# Actuator-MKI-Revision-DT.net
KiCad netlist of a schematic drawn in EAGLE
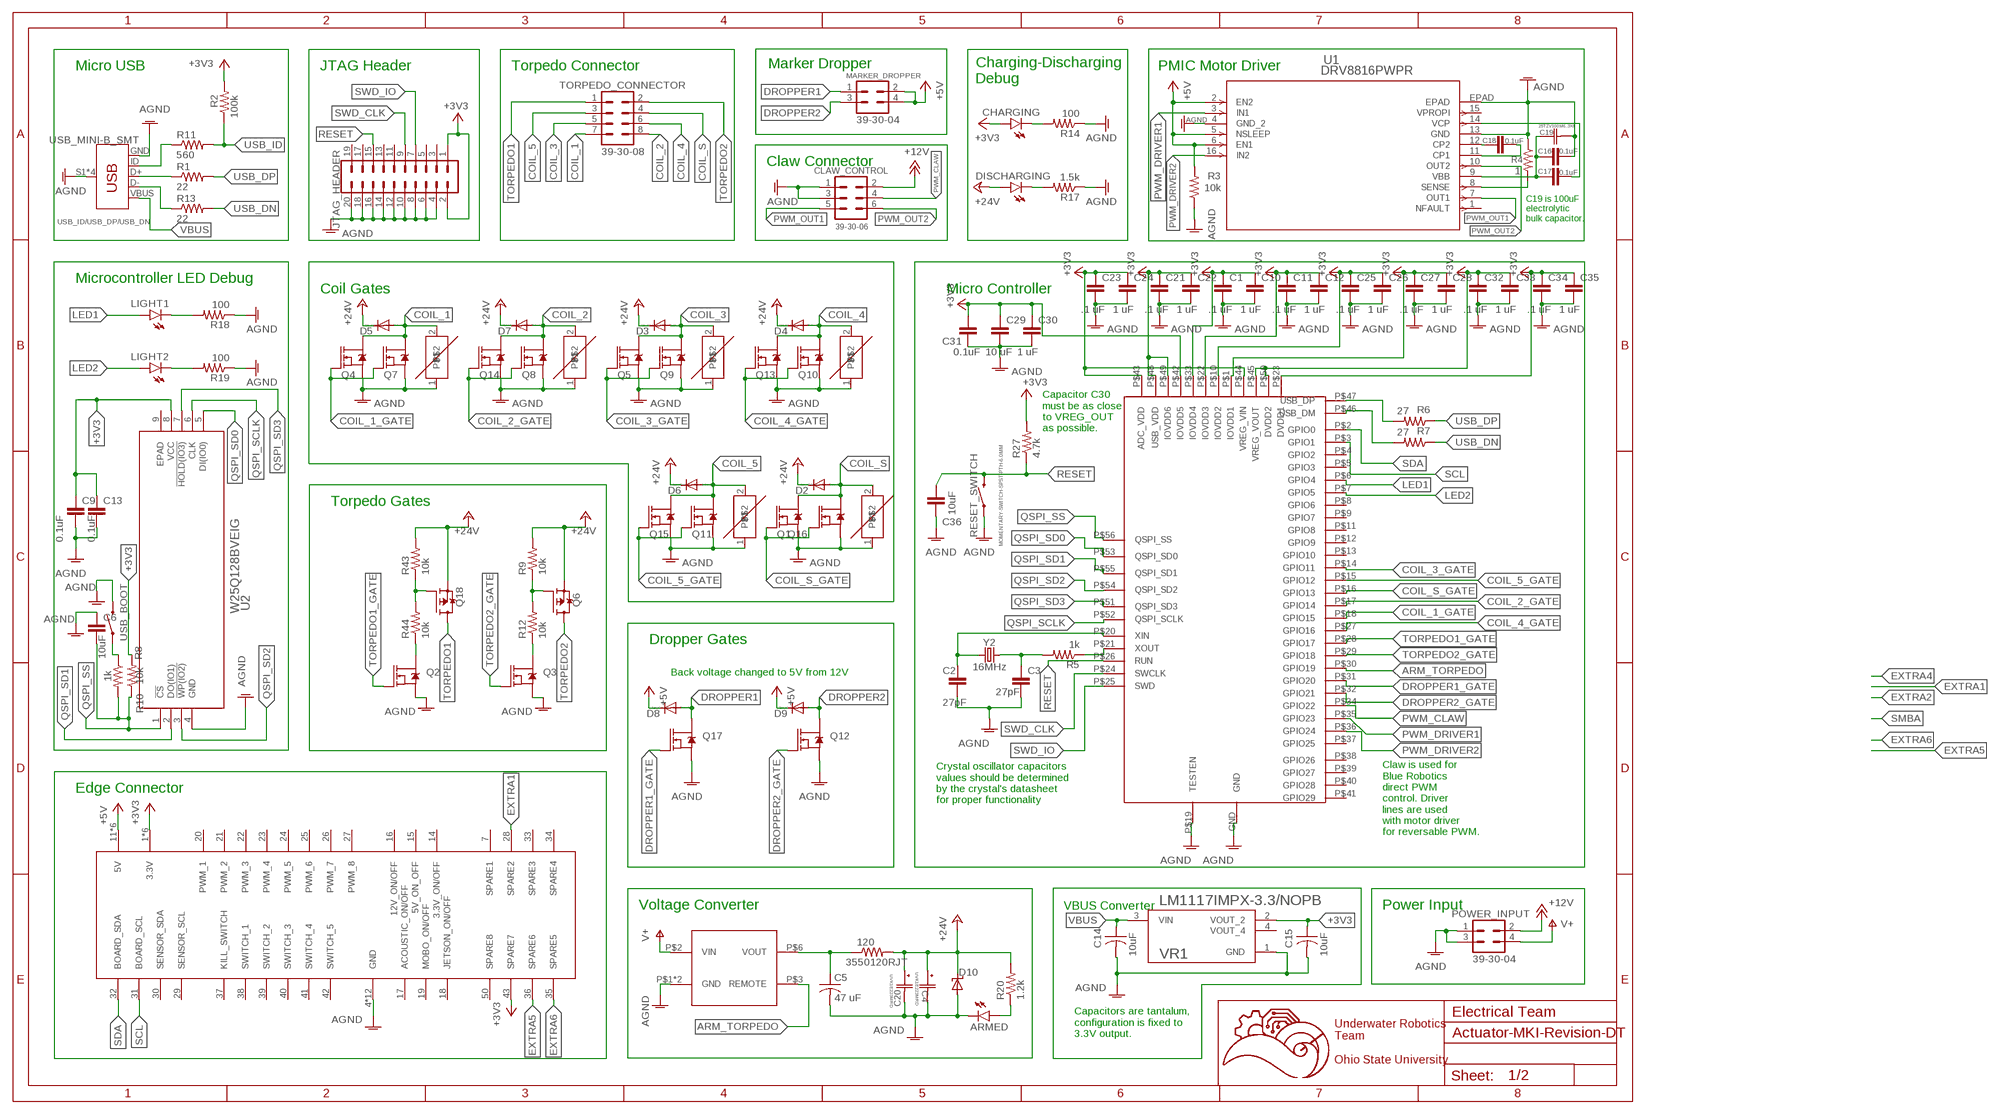
[diagram p0: schematic, sheet 1]
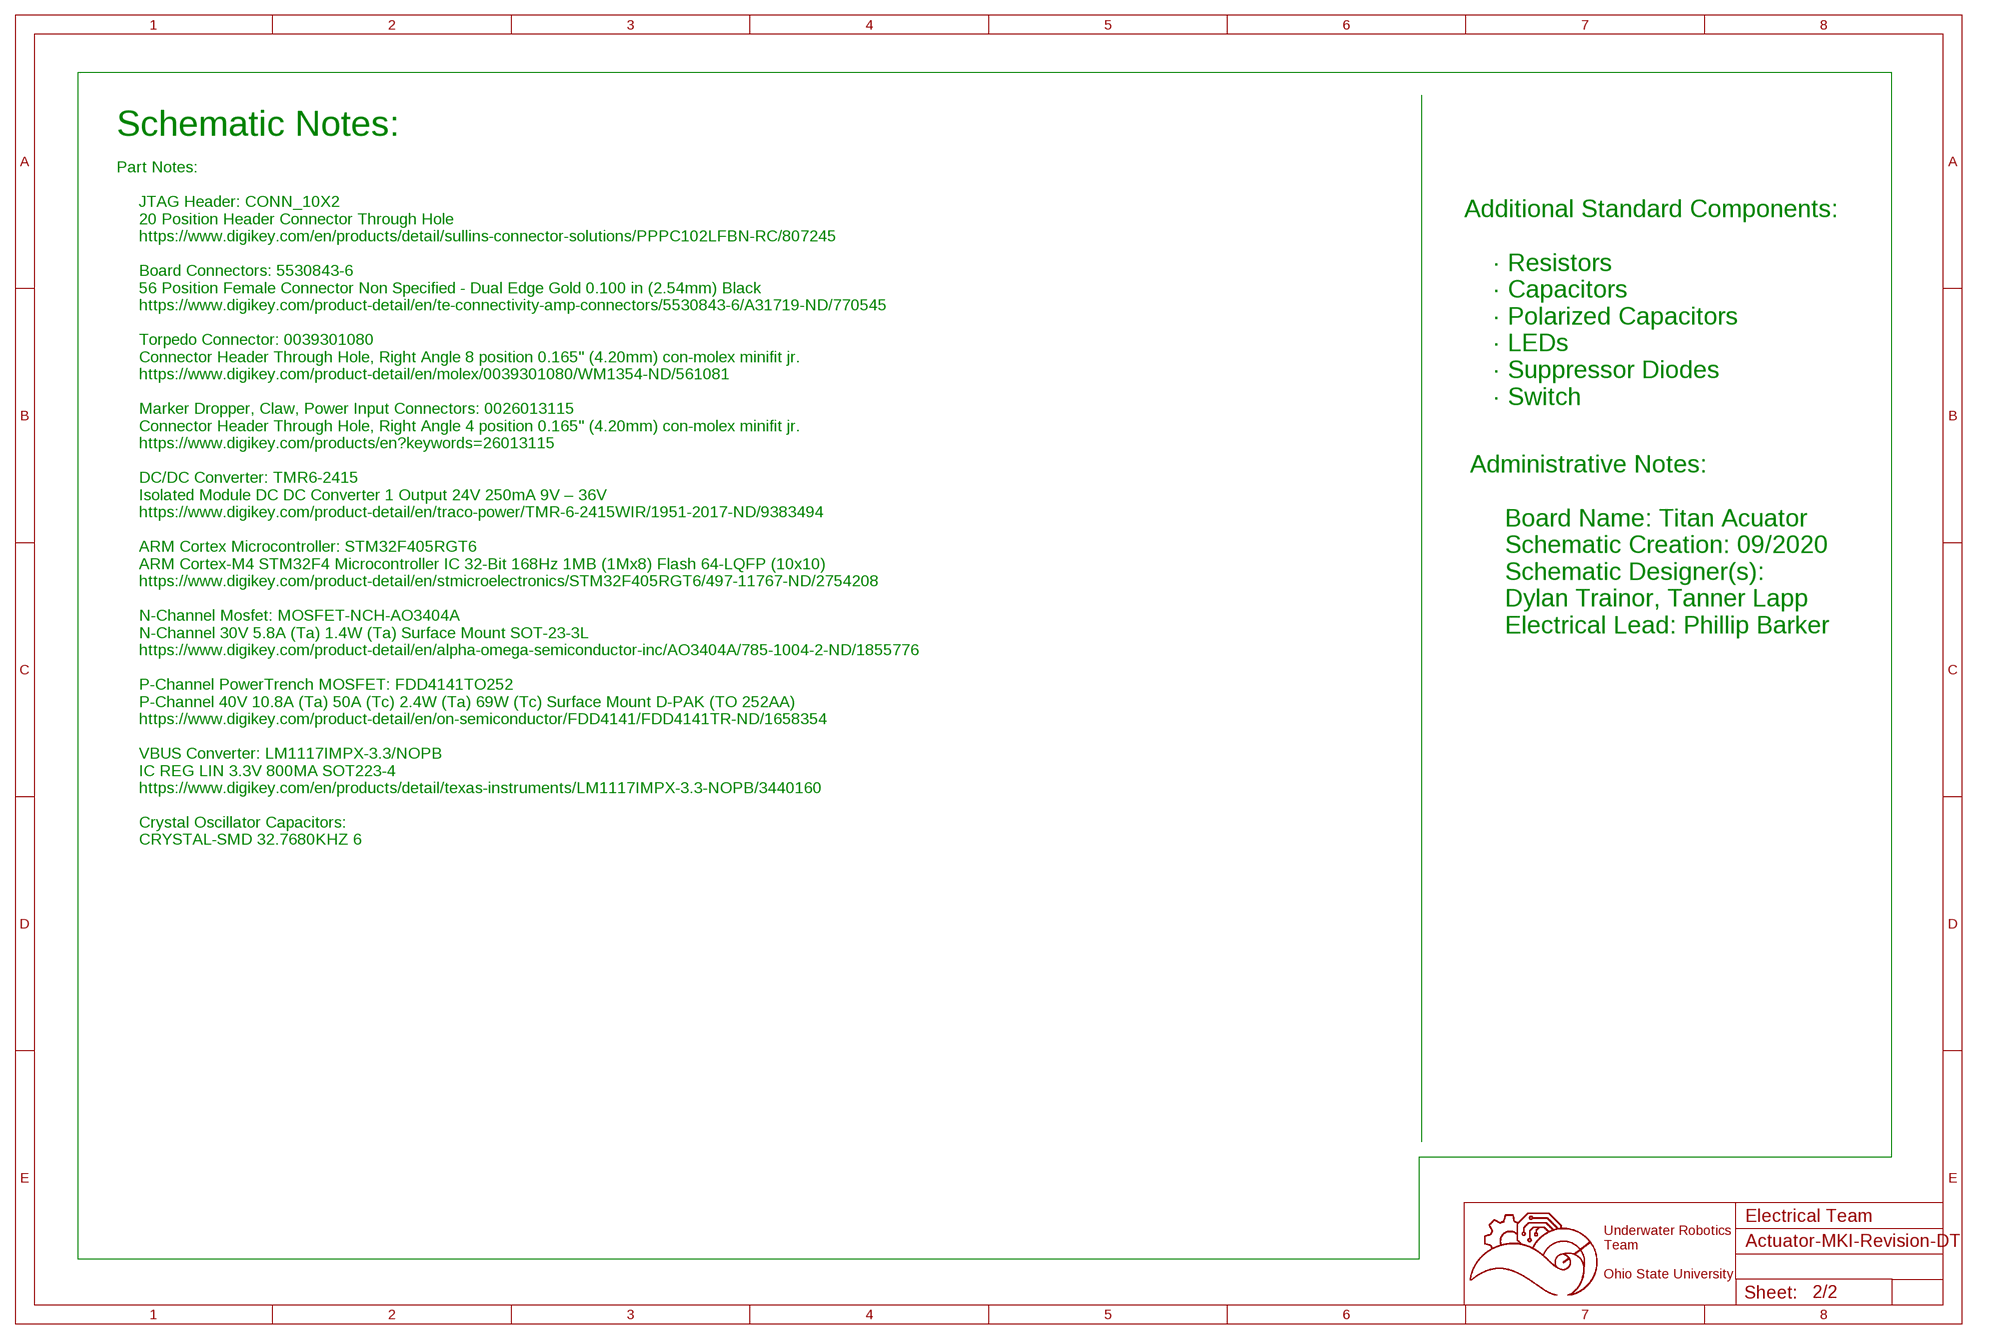
[diagram p1: schematic, sheet 2]

(export (version "E")
  (design (tool "Eeschema 10.0.6"))
  (components
    (comp (ref "120")
      (value "3550120RJT")
      (footprint "eagle-import:3550120RJT")
      (libsource (lib "eagle-import") (part "3550120RJT"))
    )
    (comp (ref "ARMED")
      (value "LEDCHIPLED_0603")
      (footprint "eagle-import:CHIPLED_0603")
      (libsource (lib "eagle-import") (part "LEDCHIPLED_0603"))
    )
    (comp (ref "C1")
      (value ".1 uF")
      (footprint "eagle-import:C0603")
      (libsource (lib "eagle-import") (part "C-EUC0603"))
    )
    (comp (ref "C2")
      (value "27pF")
      (footprint "eagle-import:C0603")
      (libsource (lib "eagle-import") (part "C-EUC0603"))
    )
    (comp (ref "C3")
      (value "27pF")
      (footprint "eagle-import:C0603")
      (libsource (lib "eagle-import") (part "C-EUC0603"))
    )
    (comp (ref "C4")
      (value "UVK1E223MRD")
      (footprint "eagle-import:CAP_UFW_25X50_NCH")
      (fields (field (name "COPYRIGHT") "Copyright (C) 2018 Accelerated Designs. All rights reserved"))
      (libsource (lib "eagle-import") (part "UVK1E223MRD"))
    )
    (comp (ref "C5")
      (value "47 uF")
      (footprint "eagle-import:C1206K")
      (libsource (lib "eagle-import") (part "resistor_348_C-USC1206K"))
    )
    (comp (ref "C6")
      (value "10uF")
      (footprint "eagle-import:C0603")
      (libsource (lib "eagle-import") (part "C-EUC0603"))
    )
    (comp (ref "C9")
      (value "0.1uF")
      (footprint "eagle-import:C0603")
      (libsource (lib "eagle-import") (part "C-EUC0603"))
    )
    (comp (ref "C10")
      (value "1 uF")
      (footprint "eagle-import:C0603")
      (libsource (lib "eagle-import") (part "C-EUC0603"))
    )
    (comp (ref "C11")
      (value ".1 uF")
      (footprint "eagle-import:C0603")
      (libsource (lib "eagle-import") (part "C-EUC0603"))
    )
    (comp (ref "C12")
      (value "1 uF")
      (footprint "eagle-import:C0603")
      (libsource (lib "eagle-import") (part "C-EUC0603"))
    )
    (comp (ref "C13")
      (value "0.1uF")
      (footprint "eagle-import:C0603")
      (libsource (lib "eagle-import") (part "C-EUC0603"))
    )
    (comp (ref "C14")
      (value "10uF")
      (footprint "eagle-import:C0603")
      (libsource (lib "eagle-import") (part "C-USC0603"))
    )
    (comp (ref "C15")
      (value "10uF")
      (footprint "eagle-import:C0603")
      (libsource (lib "eagle-import") (part "C-USC0603"))
    )
    (comp (ref "C16")
      (value "0.1uF")
      (footprint "eagle-import:C0603")
      (libsource (lib "eagle-import") (part "C-EUC0603"))
    )
    (comp (ref "C17")
      (value "0.1uF")
      (footprint "eagle-import:C0603")
      (libsource (lib "eagle-import") (part "C-EUC0603"))
    )
    (comp (ref "C18")
      (value "0.1uF")
      (footprint "eagle-import:C0603")
      (libsource (lib "eagle-import") (part "C-EUC0603"))
    )
    (comp (ref "C19")
      (value "25TZV100M6.3X8")
      (footprint "eagle-import:CAP_J-V_6P3X8_RUB")
      (fields (field (name "COPYRIGHT") "Copyright (C) 2018 Accelerated Designs. All rights reserved"))
      (libsource (lib "eagle-import") (part "25TZV100M6.3X8"))
    )
    (comp (ref "C20")
      (value "UVK1E223MRD")
      (footprint "eagle-import:CAP_UFW_25X50_NCH")
      (fields (field (name "COPYRIGHT") "Copyright (C) 2018 Accelerated Designs. All rights reserved"))
      (libsource (lib "eagle-import") (part "UVK1E223MRD"))
    )
    (comp (ref "C21")
      (value ".1 uF")
      (footprint "eagle-import:C0603")
      (libsource (lib "eagle-import") (part "C-EUC0603"))
    )
    (comp (ref "C22")
      (value "1 uF")
      (footprint "eagle-import:C0603")
      (libsource (lib "eagle-import") (part "C-EUC0603"))
    )
    (comp (ref "C23")
      (value ".1 uF")
      (footprint "eagle-import:C0603")
      (libsource (lib "eagle-import") (part "C-EUC0603"))
    )
    (comp (ref "C24")
      (value "1 uF")
      (footprint "eagle-import:C0603")
      (libsource (lib "eagle-import") (part "C-EUC0603"))
    )
    (comp (ref "C25")
      (value ".1 uF")
      (footprint "eagle-import:C0603")
      (libsource (lib "eagle-import") (part "C-EUC0603"))
    )
    (comp (ref "C26")
      (value "1 uF")
      (footprint "eagle-import:C0603")
      (libsource (lib "eagle-import") (part "C-EUC0603"))
    )
    (comp (ref "C27")
      (value ".1 uF")
      (footprint "eagle-import:C0603")
      (libsource (lib "eagle-import") (part "C-EUC0603"))
    )
    (comp (ref "C28")
      (value "1 uF")
      (footprint "eagle-import:C0603")
      (libsource (lib "eagle-import") (part "C-EUC0603"))
    )
    (comp (ref "C29")
      (value "10 uF")
      (footprint "eagle-import:C0603")
      (libsource (lib "eagle-import") (part "C-EUC0603"))
    )
    (comp (ref "C30")
      (value "1 uF")
      (footprint "eagle-import:C0603")
      (libsource (lib "eagle-import") (part "C-EUC0603"))
    )
    (comp (ref "C31")
      (value "0.1uF")
      (footprint "eagle-import:C0603")
      (libsource (lib "eagle-import") (part "C-EUC0603"))
    )
    (comp (ref "C32")
      (value ".1 uF")
      (footprint "eagle-import:C0603")
      (libsource (lib "eagle-import") (part "C-EUC0603"))
    )
    (comp (ref "C33")
      (value "1 uF")
      (footprint "eagle-import:C0603")
      (libsource (lib "eagle-import") (part "C-EUC0603"))
    )
    (comp (ref "C34")
      (value ".1 uF")
      (footprint "eagle-import:C0603")
      (libsource (lib "eagle-import") (part "C-EUC0603"))
    )
    (comp (ref "C35")
      (value "1 uF")
      (footprint "eagle-import:C0603")
      (libsource (lib "eagle-import") (part "C-EUC0603"))
    )
    (comp (ref "C36")
      (value "10uF")
      (footprint "eagle-import:C0603")
      (libsource (lib "eagle-import") (part "C-EUC0603"))
    )
    (comp (ref "CHARGING")
      (value "LEDCHIPLED_0603")
      (footprint "eagle-import:CHIPLED_0603")
      (libsource (lib "eagle-import") (part "LEDCHIPLED_0603"))
    )
    (comp (ref "CLAW_CONTROL")
      (value "39-30-06")
      (footprint "eagle-import:39-30-_06_")
      (libsource (lib "eagle-import") (part "39-30-?06?"))
    )
    (comp (ref "D2")
      (value "DIODE-SMB")
      (footprint "eagle-import:SMB")
      (libsource (lib "eagle-import") (part "DIODE-SMB"))
    )
    (comp (ref "D3")
      (value "DIODE-SMB")
      (footprint "eagle-import:SMB")
      (libsource (lib "eagle-import") (part "DIODE-SMB"))
    )
    (comp (ref "D4")
      (value "DIODE-SMB")
      (footprint "eagle-import:SMB")
      (libsource (lib "eagle-import") (part "DIODE-SMB"))
    )
    (comp (ref "D5")
      (value "DIODE-SMB")
      (footprint "eagle-import:SMB")
      (libsource (lib "eagle-import") (part "DIODE-SMB"))
    )
    (comp (ref "D6")
      (value "DIODE-SMB")
      (footprint "eagle-import:SMB")
      (libsource (lib "eagle-import") (part "DIODE-SMB"))
    )
    (comp (ref "D7")
      (value "DIODE-SMB")
      (footprint "eagle-import:SMB")
      (libsource (lib "eagle-import") (part "DIODE-SMB"))
    )
    (comp (ref "D8")
      (value "DIODE-SMB")
      (footprint "eagle-import:SMB")
      (libsource (lib "eagle-import") (part "DIODE-SMB"))
    )
    (comp (ref "D9")
      (value "DIODE-SMB")
      (footprint "eagle-import:SMB")
      (libsource (lib "eagle-import") (part "DIODE-SMB"))
    )
    (comp (ref "D10")
      (value "SUPPRESSOR-SMBJ")
      (footprint "eagle-import:SMBJ")
      (libsource (lib "eagle-import") (part "SUPPRESSOR-SMBJ"))
    )
    (comp (ref "DISCHARGING")
      (value "LEDCHIPLED_0603")
      (footprint "eagle-import:CHIPLED_0603")
      (libsource (lib "eagle-import") (part "LEDCHIPLED_0603"))
    )
    (comp (ref "JTAG_HEADER")
      (value "CONN_10X2")
      (footprint "eagle-import:2X10")
      (libsource (lib "eagle-import") (part "CONN_10X2"))
    )
    (comp (ref "LIGHT1")
      (value "LEDCHIPLED_0603")
      (footprint "eagle-import:CHIPLED_0603")
      (libsource (lib "eagle-import") (part "LEDCHIPLED_0603"))
    )
    (comp (ref "LIGHT2")
      (value "LEDCHIPLED_0603")
      (footprint "eagle-import:CHIPLED_0603")
      (libsource (lib "eagle-import") (part "LEDCHIPLED_0603"))
    )
    (comp (ref "MARKER_DROPPER")
      (value "39-30-04")
      (footprint "eagle-import:39-30-_04_")
      (libsource (lib "eagle-import") (part "39-30-?04?"))
    )
    (comp (ref "POWER_INPUT")
      (value "39-30-04")
      (footprint "eagle-import:39-30-_04_")
      (libsource (lib "eagle-import") (part "39-30-?04?"))
    )
    (comp (ref "Q1")
      (value "MOSFET-NCH-AO3404A")
      (footprint "eagle-import:SOT23-3")
      (libsource (lib "eagle-import") (part "MOSFET-NCH-AO3404A"))
    )
    (comp (ref "Q2")
      (value "MOSFET-NCH-AO3404A")
      (footprint "eagle-import:SOT23-3")
      (libsource (lib "eagle-import") (part "MOSFET-NCH-AO3404A"))
    )
    (comp (ref "Q3")
      (value "MOSFET-NCH-AO3404A")
      (footprint "eagle-import:SOT23-3")
      (libsource (lib "eagle-import") (part "MOSFET-NCH-AO3404A"))
    )
    (comp (ref "Q4")
      (value "MOSFET-NCH-AO3404A")
      (footprint "eagle-import:SOT23-3")
      (libsource (lib "eagle-import") (part "MOSFET-NCH-AO3404A"))
    )
    (comp (ref "Q5")
      (value "MOSFET-NCH-AO3404A")
      (footprint "eagle-import:SOT23-3")
      (libsource (lib "eagle-import") (part "MOSFET-NCH-AO3404A"))
    )
    (comp (ref "Q6")
      (value "FDD4141TO252")
      (footprint "eagle-import:TO252")
      (libsource (lib "eagle-import") (part "FDD4141TO252"))
    )
    (comp (ref "Q7")
      (value "MOSFET-NCH-AO3404A")
      (footprint "eagle-import:SOT23-3")
      (libsource (lib "eagle-import") (part "MOSFET-NCH-AO3404A"))
    )
    (comp (ref "Q8")
      (value "MOSFET-NCH-AO3404A")
      (footprint "eagle-import:SOT23-3")
      (libsource (lib "eagle-import") (part "MOSFET-NCH-AO3404A"))
    )
    (comp (ref "Q9")
      (value "MOSFET-NCH-AO3404A")
      (footprint "eagle-import:SOT23-3")
      (libsource (lib "eagle-import") (part "MOSFET-NCH-AO3404A"))
    )
    (comp (ref "Q10")
      (value "MOSFET-NCH-AO3404A")
      (footprint "eagle-import:SOT23-3")
      (libsource (lib "eagle-import") (part "MOSFET-NCH-AO3404A"))
    )
    (comp (ref "Q11")
      (value "MOSFET-NCH-AO3404A")
      (footprint "eagle-import:SOT23-3")
      (libsource (lib "eagle-import") (part "MOSFET-NCH-AO3404A"))
    )
    (comp (ref "Q12")
      (value "MOSFET-NCH-AO3404A")
      (footprint "eagle-import:SOT23-3")
      (libsource (lib "eagle-import") (part "MOSFET-NCH-AO3404A"))
    )
    (comp (ref "Q13")
      (value "MOSFET-NCH-AO3404A")
      (footprint "eagle-import:SOT23-3")
      (libsource (lib "eagle-import") (part "MOSFET-NCH-AO3404A"))
    )
    (comp (ref "Q14")
      (value "MOSFET-NCH-AO3404A")
      (footprint "eagle-import:SOT23-3")
      (libsource (lib "eagle-import") (part "MOSFET-NCH-AO3404A"))
    )
    (comp (ref "Q15")
      (value "MOSFET-NCH-AO3404A")
      (footprint "eagle-import:SOT23-3")
      (libsource (lib "eagle-import") (part "MOSFET-NCH-AO3404A"))
    )
    (comp (ref "Q16")
      (value "MOSFET-NCH-AO3404A")
      (footprint "eagle-import:SOT23-3")
      (libsource (lib "eagle-import") (part "MOSFET-NCH-AO3404A"))
    )
    (comp (ref "Q17")
      (value "MOSFET-NCH-AO3404A")
      (footprint "eagle-import:SOT23-3")
      (libsource (lib "eagle-import") (part "MOSFET-NCH-AO3404A"))
    )
    (comp (ref "Q18")
      (value "FDD4141TO252")
      (footprint "eagle-import:TO252")
      (libsource (lib "eagle-import") (part "FDD4141TO252"))
    )
    (comp (ref "R1")
      (value "22")
      (footprint "eagle-import:R0603")
      (libsource (lib "eagle-import") (part "R-US_R0603"))
    )
    (comp (ref "R2")
      (value "100k")
      (footprint "eagle-import:R0603")
      (libsource (lib "eagle-import") (part "R-US_R0603"))
    )
    (comp (ref "R3")
      (value "10k")
      (footprint "eagle-import:R0603")
      (libsource (lib "eagle-import") (part "resistor_348_R-US_R0603"))
    )
    (comp (ref "R4")
      (value "1")
      (footprint "eagle-import:R0805")
      (libsource (lib "eagle-import") (part "resistor_348_R-US_R0805"))
    )
    (comp (ref "R5")
      (value "1k")
      (footprint "eagle-import:R0603")
      (libsource (lib "eagle-import") (part "R-US_R0603"))
    )
    (comp (ref "R6")
      (value "27")
      (footprint "eagle-import:R0603")
      (libsource (lib "eagle-import") (part "R-US_R0603"))
    )
    (comp (ref "R7")
      (value "27")
      (footprint "eagle-import:R0603")
      (libsource (lib "eagle-import") (part "R-US_R0603"))
    )
    (comp (ref "R8")
      (value "10k")
      (footprint "eagle-import:R0603")
      (libsource (lib "eagle-import") (part "resistor_348_R-US_R0603"))
    )
    (comp (ref "R9")
      (value "10k")
      (footprint "eagle-import:R0603")
      (libsource (lib "eagle-import") (part "resistor_348_R-US_R0603"))
    )
    (comp (ref "R10")
      (value "1k")
      (footprint "eagle-import:R0603")
      (libsource (lib "eagle-import") (part "R-US_R0603"))
    )
    (comp (ref "R11")
      (value "560")
      (footprint "eagle-import:R0603")
      (libsource (lib "eagle-import") (part "R-US_R0603"))
    )
    (comp (ref "R12")
      (value "10k")
      (footprint "eagle-import:R0603")
      (libsource (lib "eagle-import") (part "resistor_348_R-US_R0603"))
    )
    (comp (ref "R13")
      (value "22")
      (footprint "eagle-import:R0603")
      (libsource (lib "eagle-import") (part "R-US_R0603"))
    )
    (comp (ref "R14")
      (value "100")
      (footprint "eagle-import:R0805")
      (libsource (lib "eagle-import") (part "resistor_348_R-US_R0805"))
    )
    (comp (ref "R17")
      (value "1.5k")
      (footprint "eagle-import:R0805")
      (libsource (lib "eagle-import") (part "resistor_348_R-US_R0805"))
    )
    (comp (ref "R18")
      (value "100")
      (footprint "eagle-import:R0805")
      (libsource (lib "eagle-import") (part "resistor_348_R-US_R0805"))
    )
    (comp (ref "R19")
      (value "100")
      (footprint "eagle-import:R0805")
      (libsource (lib "eagle-import") (part "resistor_348_R-US_R0805"))
    )
    (comp (ref "R20")
      (value "1.2k")
      (footprint "eagle-import:R0805")
      (libsource (lib "eagle-import") (part "resistor_348_R-US_R0805"))
    )
    (comp (ref "R27")
      (value "4.7k")
      (footprint "eagle-import:R0603")
      (libsource (lib "eagle-import") (part "R-US_R0603"))
    )
    (comp (ref "R43")
      (value "10k")
      (footprint "eagle-import:R0603")
      (libsource (lib "eagle-import") (part "resistor_348_R-US_R0603"))
    )
    (comp (ref "R44")
      (value "10k")
      (footprint "eagle-import:R0603")
      (libsource (lib "eagle-import") (part "resistor_348_R-US_R0603"))
    )
    (comp (ref "RESET_SWITCH")
      (value "MOMENTARY-SWITCH-SPST-PTH-6.0MM")
      (footprint "eagle-import:TACTILE_SWITCH_PTH_6.0MM")
      (libsource (lib "eagle-import") (part "MOMENTARY-SWITCH-SPST-PTH-6.0MM"))
    )
    (comp (ref "TORPEDO_CONNECTOR")
      (value "39-30-08")
      (footprint "eagle-import:39-30-_08_")
      (libsource (lib "eagle-import") (part "39-30-?08?"))
    )
    (comp (ref "U$1")
      (value "5530843-EDGE")
      (footprint "eagle-import:5530843-6-BOARDFINGERS")
      (libsource (lib "eagle-import") (part "5530843-EDGE"))
    )
    (comp (ref "U$2")
      (value "ERZ-VF2M270ERZ-VF2M270")
      (footprint "eagle-import:RESM8060X320N")
      (libsource (lib "eagle-import") (part "ERZ-VF2M270ERZ-VF2M270"))
    )
    (comp (ref "U$3")
      (value "ERZ-VF2M270ERZ-VF2M270")
      (footprint "eagle-import:RESM8060X320N")
      (libsource (lib "eagle-import") (part "ERZ-VF2M270ERZ-VF2M270"))
    )
    (comp (ref "U$4")
      (value "ERZ-VF2M270ERZ-VF2M270")
      (footprint "eagle-import:RESM8060X320N")
      (libsource (lib "eagle-import") (part "ERZ-VF2M270ERZ-VF2M270"))
    )
    (comp (ref "U$5")
      (value "ERZ-VF2M270ERZ-VF2M270")
      (footprint "eagle-import:RESM8060X320N")
      (libsource (lib "eagle-import") (part "ERZ-VF2M270ERZ-VF2M270"))
    )
    (comp (ref "U$6")
      (value "TMR6-2415")
      (footprint "eagle-import:TMR6-2415")
      (libsource (lib "eagle-import") (part "TMR6-2415"))
    )
    (comp (ref "U$7")
      (value "ERZ-VF2M270ERZ-VF2M270")
      (footprint "eagle-import:RESM8060X320N")
      (libsource (lib "eagle-import") (part "ERZ-VF2M270ERZ-VF2M270"))
    )
    (comp (ref "U$8")
      (value "ERZ-VF2M270ERZ-VF2M270")
      (footprint "eagle-import:RESM8060X320N")
      (libsource (lib "eagle-import") (part "ERZ-VF2M270ERZ-VF2M270"))
    )
    (comp (ref "U$9")
      (value "RP2040")
      (footprint "eagle-import:RP2040")
      (libsource (lib "eagle-import") (part "RP2040"))
    )
    (comp (ref "U1")
      (value "DRV8816PWPR")
      (footprint "eagle-import:PWP_16")
      (libsource (lib "eagle-import") (part "DRV8816PWPR"))
    )
    (comp (ref "U2")
      (value "W25Q128BVEIG")
      (footprint "eagle-import:WIN_E-8_WIN")
      (fields (field (name "COPYRIGHT") "Copyright (C) 2021 Ultra Librarian. All rights reserved."))
      (libsource (lib "eagle-import") (part "W25Q128BVEIG"))
    )
    (comp (ref "USB_BOOT")
      (value "MOMENTARY-SWITCH-SPST-PTH-6.0MM")
      (footprint "eagle-import:TACTILE_SWITCH_PTH_6.0MM")
      (libsource (lib "eagle-import") (part "MOMENTARY-SWITCH-SPST-PTH-6.0MM"))
    )
    (comp (ref "USB_ID/USB_DP/USB_DN")
      (value "USB_MINI-B_SMT")
      (footprint "eagle-import:USB-MINIB")
      (libsource (lib "eagle-import") (part "USB_MINI-B_SMT"))
    )
    (comp (ref "VR1")
      (value "LM1117IMPX-3.3/NOPB")
      (footprint "eagle-import:VREG_LM1117IMPX-3.3_NOPB")
      (fields (field (name "MF") "Texas Instruments"))
      (libsource (lib "eagle-import") (part "LM1117IMPX-3.3/NOPB"))
    )
    (comp (ref "Y2")
      (value "16MHz")
      (footprint "eagle-import:HC49US")
      (libsource (lib "eagle-import") (part "CRYSTAL-16MHZPTH-HC49US"))
    )
  )
  (nets
    (net (code "1") (name "+3V3") (class "Default")
      (node (ref "C1") (pin "1") (pinfunction "1_1") (pintype "passive"))
      (node (ref "C10") (pin "1") (pinfunction "1_1") (pintype "passive"))
      (node (ref "C11") (pin "1") (pinfunction "1_1") (pintype "passive"))
      (node (ref "C12") (pin "1") (pinfunction "1_1") (pintype "passive"))
      (node (ref "C13") (pin "1") (pinfunction "1_1") (pintype "passive"))
      (node (ref "C15") (pin "1") (pinfunction "1_1") (pintype "passive"))
      (node (ref "C21") (pin "1") (pinfunction "1_1") (pintype "passive"))
      (node (ref "C22") (pin "1") (pinfunction "1_1") (pintype "passive"))
      (node (ref "C23") (pin "1") (pinfunction "1_1") (pintype "passive"))
      (node (ref "C24") (pin "1") (pinfunction "1_1") (pintype "passive"))
      (node (ref "C25") (pin "1") (pinfunction "1_1") (pintype "passive"))
      (node (ref "C26") (pin "1") (pinfunction "1_1") (pintype "passive"))
      (node (ref "C27") (pin "1") (pinfunction "1_1") (pintype "passive"))
      (node (ref "C28") (pin "1") (pinfunction "1_1") (pintype "passive"))
      (node (ref "C29") (pin "1") (pinfunction "1_1") (pintype "passive"))
      (node (ref "C30") (pin "1") (pinfunction "1_1") (pintype "passive"))
      (node (ref "C31") (pin "2") (pinfunction "2_2") (pintype "passive"))
      (node (ref "C32") (pin "1") (pinfunction "1_1") (pintype "passive"))
      (node (ref "C33") (pin "1") (pinfunction "1_1") (pintype "passive"))
      (node (ref "C34") (pin "1") (pinfunction "1_1") (pintype "passive"))
      (node (ref "C35") (pin "1") (pinfunction "1_1") (pintype "passive"))
      (node (ref "C9") (pin "1") (pinfunction "1_1") (pintype "passive"))
      (node (ref "CHARGING") (pin "A") (pinfunction "A_A") (pintype "passive"))
      (node (ref "JTAG_HEADER") (pin "1") (pinfunction "1_1") (pintype "passive"))
      (node (ref "JTAG_HEADER") (pin "2") (pinfunction "2_2") (pintype "passive"))
      (node (ref "R2") (pin "2") (pinfunction "2_2") (pintype "passive"))
      (node (ref "R27") (pin "2") (pinfunction "2_2") (pintype "passive"))
      (node (ref "R8") (pin "2") (pinfunction "2_2") (pintype "passive"))
      (node (ref "U$1") (pin "1") (pinfunction "3.3V_1") (pintype "bidirectional"))
      (node (ref "U$1") (pin "2") (pinfunction "3.3V_2") (pintype "bidirectional"))
      (node (ref "U$1") (pin "3") (pinfunction "3.3V_3") (pintype "bidirectional"))
      (node (ref "U$1") (pin "43") (pinfunction "SPARE7_43") (pintype "bidirectional"))
      (node (ref "U$1") (pin "54") (pinfunction "3.3V_54") (pintype "bidirectional"))
      (node (ref "U$1") (pin "55") (pinfunction "3.3V_55") (pintype "bidirectional"))
      (node (ref "U$1") (pin "56") (pinfunction "3.3V_56") (pintype "bidirectional"))
      (node (ref "U$9") (pin "P$1") (pinfunction "IOVDD1_P$1") (pintype "bidirectional"))
      (node (ref "U$9") (pin "P$10") (pinfunction "IOVDD2_P$10") (pintype "bidirectional"))
      (node (ref "U$9") (pin "P$22") (pinfunction "IOVDD3_P$22") (pintype "bidirectional"))
      (node (ref "U$9") (pin "P$23") (pinfunction "DVDD1_P$23") (pintype "bidirectional"))
      (node (ref "U$9") (pin "P$33") (pinfunction "IOVDD4_P$33") (pintype "bidirectional"))
      (node (ref "U$9") (pin "P$42") (pinfunction "IOVDD5_P$42") (pintype "bidirectional"))
      (node (ref "U$9") (pin "P$43") (pinfunction "ADC_VDD_P$43") (pintype "bidirectional"))
      (node (ref "U$9") (pin "P$44") (pinfunction "VREG_VIN_P$44") (pintype "bidirectional"))
      (node (ref "U$9") (pin "P$45") (pinfunction "VREG_VOUT_P$45") (pintype "bidirectional"))
      (node (ref "U$9") (pin "P$48") (pinfunction "USB_VDD_P$48") (pintype "bidirectional"))
      (node (ref "U$9") (pin "P$49") (pinfunction "IOVDD6_P$49") (pintype "bidirectional"))
      (node (ref "U$9") (pin "P$50") (pinfunction "DVDD2_P$50") (pintype "bidirectional"))
      (node (ref "U2") (pin "8") (pinfunction "VCC_8") (pintype "power_in"))
      (node (ref "VR1") (pin "2") (pinfunction "VOUT_2_2") (pintype "output"))
    )
    (net (code "2") (name "+5V") (class "Default")
      (node (ref "D8") (pin "C") (pinfunction "C_C") (pintype "passive"))
      (node (ref "D9") (pin "C") (pinfunction "C_C") (pintype "passive"))
      (node (ref "MARKER_DROPPER") (pin "2") (pinfunction "2_2") (pintype "passive"))
      (node (ref "MARKER_DROPPER") (pin "4") (pinfunction "4_4") (pintype "passive"))
      (node (ref "R3") (pin "2") (pinfunction "2_2") (pintype "passive"))
      (node (ref "U$1") (pin "11") (pinfunction "5V_11") (pintype "bidirectional"))
      (node (ref "U$1") (pin "12") (pinfunction "5V_12") (pintype "bidirectional"))
      (node (ref "U$1") (pin "13") (pinfunction "5V_13") (pintype "bidirectional"))
      (node (ref "U$1") (pin "44") (pinfunction "5V_44") (pintype "bidirectional"))
      (node (ref "U$1") (pin "45") (pinfunction "5V_45") (pintype "bidirectional"))
      (node (ref "U$1") (pin "46") (pinfunction "5V_46") (pintype "bidirectional"))
      (node (ref "U1") (pin "2") (pinfunction "EN2_2") (pintype "input"))
      (node (ref "U1") (pin "5") (pinfunction "NSLEEP_5") (pintype "input"))
      (node (ref "U1") (pin "6") (pinfunction "EN1_6") (pintype "input"))
    )
    (net (code "3") (name "+12V") (class "Default")
      (node (ref "CLAW_CONTROL") (pin "2") (pinfunction "2_2") (pintype "passive"))
      (node (ref "POWER_INPUT") (pin "2") (pinfunction "2_2") (pintype "passive"))
    )
    (net (code "4") (name "+24V") (class "Default")
      (node (ref "120") (pin "P$2") (pinfunction "2_P$2") (pintype "passive"))
      (node (ref "C20") (pin "1") (pinfunction "1_1") (pintype "passive"))
      (node (ref "C4") (pin "1") (pinfunction "1_1") (pintype "passive"))
      (node (ref "D10") (pin "C") (pinfunction "C_C") (pintype "passive"))
      (node (ref "D2") (pin "C") (pinfunction "C_C") (pintype "passive"))
      (node (ref "D3") (pin "C") (pinfunction "C_C") (pintype "passive"))
      (node (ref "D4") (pin "C") (pinfunction "C_C") (pintype "passive"))
      (node (ref "D5") (pin "C") (pinfunction "C_C") (pintype "passive"))
      (node (ref "D6") (pin "C") (pinfunction "C_C") (pintype "passive"))
      (node (ref "D7") (pin "C") (pinfunction "C_C") (pintype "passive"))
      (node (ref "DISCHARGING") (pin "A") (pinfunction "A_A") (pintype "passive"))
      (node (ref "Q18") (pin "2") (pinfunction "S_2") (pintype "passive"))
      (node (ref "Q6") (pin "2") (pinfunction "S_2") (pintype "passive"))
      (node (ref "R20") (pin "2") (pinfunction "2_2") (pintype "passive"))
      (node (ref "R43") (pin "2") (pinfunction "2_2") (pintype "passive"))
      (node (ref "R9") (pin "2") (pinfunction "2_2") (pintype "passive"))
    )
    (net (code "5") (name "AGND") (class "Default")
      (node (ref "ARMED") (pin "C") (pinfunction "C_C") (pintype "passive"))
      (node (ref "C1") (pin "2") (pinfunction "2_2") (pintype "passive"))
      (node (ref "C10") (pin "2") (pinfunction "2_2") (pintype "passive"))
      (node (ref "C11") (pin "2") (pinfunction "2_2") (pintype "passive"))
      (node (ref "C12") (pin "2") (pinfunction "2_2") (pintype "passive"))
      (node (ref "C13") (pin "2") (pinfunction "2_2") (pintype "passive"))
      (node (ref "C14") (pin "2") (pinfunction "2_2") (pintype "passive"))
      (node (ref "C15") (pin "2") (pinfunction "2_2") (pintype "passive"))
      (node (ref "C16") (pin "2") (pinfunction "2_2") (pintype "passive"))
      (node (ref "C19") (pin "2") (pinfunction "2_2") (pintype "passive"))
      (node (ref "C2") (pin "2") (pinfunction "2_2") (pintype "passive"))
      (node (ref "C20") (pin "2") (pinfunction "2_2") (pintype "passive"))
      (node (ref "C21") (pin "2") (pinfunction "2_2") (pintype "passive"))
      (node (ref "C22") (pin "2") (pinfunction "2_2") (pintype "passive"))
      (node (ref "C23") (pin "2") (pinfunction "2_2") (pintype "passive"))
      (node (ref "C24") (pin "2") (pinfunction "2_2") (pintype "passive"))
      (node (ref "C25") (pin "2") (pinfunction "2_2") (pintype "passive"))
      (node (ref "C26") (pin "2") (pinfunction "2_2") (pintype "passive"))
      (node (ref "C27") (pin "2") (pinfunction "2_2") (pintype "passive"))
      (node (ref "C28") (pin "2") (pinfunction "2_2") (pintype "passive"))
      (node (ref "C29") (pin "2") (pinfunction "2_2") (pintype "passive"))
      (node (ref "C3") (pin "2") (pinfunction "2_2") (pintype "passive"))
      (node (ref "C30") (pin "2") (pinfunction "2_2") (pintype "passive"))
      (node (ref "C31") (pin "1") (pinfunction "1_1") (pintype "passive"))
      (node (ref "C32") (pin "2") (pinfunction "2_2") (pintype "passive"))
      (node (ref "C33") (pin "2") (pinfunction "2_2") (pintype "passive"))
      (node (ref "C34") (pin "2") (pinfunction "2_2") (pintype "passive"))
      (node (ref "C35") (pin "2") (pinfunction "2_2") (pintype "passive"))
      (node (ref "C36") (pin "1") (pinfunction "1_1") (pintype "passive"))
      (node (ref "C4") (pin "2") (pinfunction "2_2") (pintype "passive"))
      (node (ref "C5") (pin "2") (pinfunction "2_2") (pintype "passive"))
      (node (ref "C6") (pin "1") (pinfunction "1_1") (pintype "passive"))
      (node (ref "C9") (pin "2") (pinfunction "2_2") (pintype "passive"))
      (node (ref "CLAW_CONTROL") (pin "1") (pinfunction "1_1") (pintype "passive"))
      (node (ref "CLAW_CONTROL") (pin "3") (pinfunction "3_3") (pintype "passive"))
      (node (ref "D10") (pin "A") (pinfunction "A_A") (pintype "passive"))
      (node (ref "JTAG_HEADER") (pin "10") (pinfunction "10_10") (pintype "passive"))
      (node (ref "JTAG_HEADER") (pin "12") (pinfunction "12_12") (pintype "passive"))
      (node (ref "JTAG_HEADER") (pin "14") (pinfunction "14_14") (pintype "passive"))
      (node (ref "JTAG_HEADER") (pin "16") (pinfunction "16_16") (pintype "passive"))
      (node (ref "JTAG_HEADER") (pin "18") (pinfunction "18_18") (pintype "passive"))
      (node (ref "JTAG_HEADER") (pin "20") (pinfunction "20_20") (pintype "passive"))
      (node (ref "JTAG_HEADER") (pin "4") (pinfunction "4_4") (pintype "passive"))
      (node (ref "JTAG_HEADER") (pin "6") (pinfunction "6_6") (pintype "passive"))
      (node (ref "JTAG_HEADER") (pin "8") (pinfunction "8_8") (pintype "passive"))
      (node (ref "POWER_INPUT") (pin "1") (pinfunction "1_1") (pintype "passive"))
      (node (ref "POWER_INPUT") (pin "3") (pinfunction "3_3") (pintype "passive"))
      (node (ref "Q1") (pin "2") (pinfunction "S_2") (pintype "bidirectional"))
      (node (ref "Q10") (pin "2") (pinfunction "S_2") (pintype "bidirectional"))
      (node (ref "Q11") (pin "2") (pinfunction "S_2") (pintype "bidirectional"))
      (node (ref "Q12") (pin "2") (pinfunction "S_2") (pintype "bidirectional"))
      (node (ref "Q13") (pin "2") (pinfunction "S_2") (pintype "bidirectional"))
      (node (ref "Q14") (pin "2") (pinfunction "S_2") (pintype "bidirectional"))
      (node (ref "Q15") (pin "2") (pinfunction "S_2") (pintype "bidirectional"))
      (node (ref "Q16") (pin "2") (pinfunction "S_2") (pintype "bidirectional"))
      (node (ref "Q17") (pin "2") (pinfunction "S_2") (pintype "bidirectional"))
      (node (ref "Q2") (pin "2") (pinfunction "S_2") (pintype "bidirectional"))
      (node (ref "Q3") (pin "2") (pinfunction "S_2") (pintype "bidirectional"))
      (node (ref "Q4") (pin "2") (pinfunction "S_2") (pintype "bidirectional"))
      (node (ref "Q5") (pin "2") (pinfunction "S_2") (pintype "bidirectional"))
      (node (ref "Q7") (pin "2") (pinfunction "S_2") (pintype "bidirectional"))
      (node (ref "Q8") (pin "2") (pinfunction "S_2") (pintype "bidirectional"))
      (node (ref "Q9") (pin "2") (pinfunction "S_2") (pintype "bidirectional"))
      (node (ref "R14") (pin "1") (pinfunction "1_1") (pintype "passive"))
      (node (ref "R17") (pin "1") (pinfunction "1_1") (pintype "passive"))
      (node (ref "R18") (pin "1") (pinfunction "1_1") (pintype "passive"))
      (node (ref "R19") (pin "1") (pinfunction "1_1") (pintype "passive"))
      (node (ref "R3") (pin "1") (pinfunction "1_1") (pintype "passive"))
      (node (ref "R4") (pin "1") (pinfunction "1_1") (pintype "passive"))
      (node (ref "RESET_SWITCH") (pin "1") (pinfunction "1_1") (pintype "passive"))
      (node (ref "U$1") (pin "10") (pinfunction "GND_10") (pintype "bidirectional"))
      (node (ref "U$1") (pin "4") (pinfunction "GND_4") (pintype "bidirectional"))
      (node (ref "U$1") (pin "47") (pinfunction "GND_47") (pintype "bidirectional"))
      (node (ref "U$1") (pin "48") (pinfunction "GND_48") (pintype "bidirectional"))
      (node (ref "U$1") (pin "49") (pinfunction "GND_49") (pintype "bidirectional"))
      (node (ref "U$1") (pin "5") (pinfunction "GND_5") (pintype "bidirectional"))
      (node (ref "U$1") (pin "51") (pinfunction "GND_51") (pintype "bidirectional"))
      (node (ref "U$1") (pin "52") (pinfunction "GND_52") (pintype "bidirectional"))
      (node (ref "U$1") (pin "53") (pinfunction "GND_53") (pintype "bidirectional"))
      (node (ref "U$1") (pin "6") (pinfunction "GND_6") (pintype "bidirectional"))
      (node (ref "U$1") (pin "8") (pinfunction "GND_8") (pintype "bidirectional"))
      (node (ref "U$1") (pin "9") (pinfunction "GND_9") (pintype "bidirectional"))
      (node (ref "U$2") (pin "1") (pinfunction "P$1_1") (pintype "bidirectional"))
      (node (ref "U$3") (pin "1") (pinfunction "P$1_1") (pintype "bidirectional"))
      (node (ref "U$4") (pin "1") (pinfunction "P$1_1") (pintype "bidirectional"))
      (node (ref "U$5") (pin "1") (pinfunction "P$1_1") (pintype "bidirectional"))
      (node (ref "U$6") (pin "P$1") (pinfunction "GND_P$1") (pintype "bidirectional"))
      (node (ref "U$6") (pin "P$7") (pinfunction "GND_P$7") (pintype "bidirectional"))
      (node (ref "U$7") (pin "1") (pinfunction "P$1_1") (pintype "bidirectional"))
      (node (ref "U$8") (pin "1") (pinfunction "P$1_1") (pintype "bidirectional"))
      (node (ref "U$9") (pin "GND") (pinfunction "GND_GND") (pintype "bidirectional"))
      (node (ref "U$9") (pin "P$19") (pinfunction "TESTEN_P$19") (pintype "bidirectional"))
      (node (ref "U1") (pin "13") (pinfunction "GND_13") (pintype "power_in"))
      (node (ref "U1") (pin "4") (pinfunction "GND_2_4") (pintype "power_in"))
      (node (ref "U1") (pin "EPAD") (pinfunction "EPAD_EPAD") (pintype "passive"))
      (node (ref "U2") (pin "4") (pinfunction "GND_4") (pintype "power_in"))
      (node (ref "USB_BOOT") (pin "3") (pinfunction "2_3") (pintype "passive"))
      (node (ref "USB_ID/USB_DP/USB_DN") (pin "GND") (pinfunction "GND_GND") (pintype "power_in"))
      (node (ref "USB_ID/USB_DP/USB_DN") (pin "S1") (pinfunction "SHIELD_S1") (pintype "bidirectional"))
      (node (ref "USB_ID/USB_DP/USB_DN") (pin "S2") (pinfunction "SHIELD_S2") (pintype "bidirectional"))
      (node (ref "USB_ID/USB_DP/USB_DN") (pin "S3") (pinfunction "SHIELD_S3") (pintype "bidirectional"))
      (node (ref "USB_ID/USB_DP/USB_DN") (pin "S4") (pinfunction "SHIELD_S4") (pintype "bidirectional"))
      (node (ref "VR1") (pin "1") (pinfunction "GND_1") (pintype "power_in"))
    )
    (net (code "6") (name "ARM_TORPEDO") (class "Default")
      (node (ref "U$6") (pin "P$3") (pinfunction "REMOTE_P$3") (pintype "bidirectional"))
      (node (ref "U$9") (pin "P$30") (pinfunction "GPIO19_P$30") (pintype "bidirectional"))
    )
    (net (code "7") (name "COIL_1") (class "Default")
      (node (ref "D5") (pin "A") (pinfunction "A_A") (pintype "passive"))
      (node (ref "Q4") (pin "3") (pinfunction "D_3") (pintype "bidirectional"))
      (node (ref "Q7") (pin "3") (pinfunction "D_3") (pintype "bidirectional"))
      (node (ref "TORPEDO_CONNECTOR") (pin "7") (pinfunction "7_7") (pintype "passive"))
      (node (ref "U$8") (pin "2") (pinfunction "P$2_2") (pintype "bidirectional"))
    )
    (net (code "8") (name "COIL_1_GATE") (class "Default")
      (node (ref "Q4") (pin "1") (pinfunction "G_1") (pintype "bidirectional"))
      (node (ref "Q7") (pin "1") (pinfunction "G_1") (pintype "bidirectional"))
      (node (ref "U$9") (pin "P$18") (pinfunction "GPIO15_P$18") (pintype "bidirectional"))
    )
    (net (code "9") (name "COIL_2") (class "Default")
      (node (ref "D7") (pin "A") (pinfunction "A_A") (pintype "passive"))
      (node (ref "Q14") (pin "3") (pinfunction "D_3") (pintype "bidirectional"))
      (node (ref "Q8") (pin "3") (pinfunction "D_3") (pintype "bidirectional"))
      (node (ref "TORPEDO_CONNECTOR") (pin "8") (pinfunction "8_8") (pintype "passive"))
      (node (ref "U$7") (pin "2") (pinfunction "P$2_2") (pintype "bidirectional"))
    )
    (net (code "10") (name "COIL_2_GATE") (class "Default")
      (node (ref "Q14") (pin "1") (pinfunction "G_1") (pintype "bidirectional"))
      (node (ref "Q8") (pin "1") (pinfunction "G_1") (pintype "bidirectional"))
      (node (ref "U$9") (pin "P$17") (pinfunction "GPIO14_P$17") (pintype "bidirectional"))
    )
    (net (code "11") (name "COIL_3") (class "Default")
      (node (ref "D3") (pin "A") (pinfunction "A_A") (pintype "passive"))
      (node (ref "Q5") (pin "3") (pinfunction "D_3") (pintype "bidirectional"))
      (node (ref "Q9") (pin "3") (pinfunction "D_3") (pintype "bidirectional"))
      (node (ref "TORPEDO_CONNECTOR") (pin "5") (pinfunction "5_5") (pintype "passive"))
      (node (ref "U$5") (pin "2") (pinfunction "P$2_2") (pintype "bidirectional"))
    )
    (net (code "12") (name "COIL_3_GATE") (class "Default")
      (node (ref "Q5") (pin "1") (pinfunction "G_1") (pintype "bidirectional"))
      (node (ref "Q9") (pin "1") (pinfunction "G_1") (pintype "bidirectional"))
      (node (ref "U$9") (pin "P$14") (pinfunction "GPIO11_P$14") (pintype "bidirectional"))
    )
    (net (code "13") (name "COIL_4") (class "Default")
      (node (ref "D4") (pin "A") (pinfunction "A_A") (pintype "passive"))
      (node (ref "Q10") (pin "3") (pinfunction "D_3") (pintype "bidirectional"))
      (node (ref "Q13") (pin "3") (pinfunction "D_3") (pintype "bidirectional"))
      (node (ref "TORPEDO_CONNECTOR") (pin "6") (pinfunction "6_6") (pintype "passive"))
      (node (ref "U$4") (pin "2") (pinfunction "P$2_2") (pintype "bidirectional"))
    )
    (net (code "14") (name "COIL_4_GATE") (class "Default")
      (node (ref "Q10") (pin "1") (pinfunction "G_1") (pintype "bidirectional"))
      (node (ref "Q13") (pin "1") (pinfunction "G_1") (pintype "bidirectional"))
      (node (ref "U$9") (pin "P$27") (pinfunction "GPIO16_P$27") (pintype "bidirectional"))
    )
    (net (code "15") (name "COIL_5") (class "Default")
      (node (ref "D6") (pin "A") (pinfunction "A_A") (pintype "passive"))
      (node (ref "Q11") (pin "3") (pinfunction "D_3") (pintype "bidirectional"))
      (node (ref "Q15") (pin "3") (pinfunction "D_3") (pintype "bidirectional"))
      (node (ref "TORPEDO_CONNECTOR") (pin "3") (pinfunction "3_3") (pintype "passive"))
      (node (ref "U$3") (pin "2") (pinfunction "P$2_2") (pintype "bidirectional"))
    )
    (net (code "16") (name "COIL_5_GATE") (class "Default")
      (node (ref "Q11") (pin "1") (pinfunction "G_1") (pintype "bidirectional"))
      (node (ref "Q15") (pin "1") (pinfunction "G_1") (pintype "bidirectional"))
      (node (ref "U$9") (pin "P$15") (pinfunction "GPIO12_P$15") (pintype "bidirectional"))
    )
    (net (code "17") (name "COIL_S") (class "Default")
      (node (ref "D2") (pin "A") (pinfunction "A_A") (pintype "passive"))
      (node (ref "Q1") (pin "3") (pinfunction "D_3") (pintype "bidirectional"))
      (node (ref "Q16") (pin "3") (pinfunction "D_3") (pintype "bidirectional"))
      (node (ref "TORPEDO_CONNECTOR") (pin "4") (pinfunction "4_4") (pintype "passive"))
      (node (ref "U$2") (pin "2") (pinfunction "P$2_2") (pintype "bidirectional"))
    )
    (net (code "18") (name "COIL_S_GATE") (class "Default")
      (node (ref "Q1") (pin "1") (pinfunction "G_1") (pintype "bidirectional"))
      (node (ref "Q16") (pin "1") (pinfunction "G_1") (pintype "bidirectional"))
      (node (ref "U$9") (pin "P$16") (pinfunction "GPIO13_P$16") (pintype "bidirectional"))
    )
    (net (code "19") (name "DROPPER1") (class "Default")
      (node (ref "D8") (pin "A") (pinfunction "A_A") (pintype "passive"))
      (node (ref "MARKER_DROPPER") (pin "1") (pinfunction "1_1") (pintype "passive"))
      (node (ref "Q17") (pin "3") (pinfunction "D_3") (pintype "bidirectional"))
    )
    (net (code "20") (name "DROPPER1_GATE") (class "Default")
      (node (ref "Q17") (pin "1") (pinfunction "G_1") (pintype "bidirectional"))
      (node (ref "U$9") (pin "P$31") (pinfunction "GPIO20_P$31") (pintype "bidirectional"))
    )
    (net (code "21") (name "DROPPER2") (class "Default")
      (node (ref "D9") (pin "A") (pinfunction "A_A") (pintype "passive"))
      (node (ref "MARKER_DROPPER") (pin "3") (pinfunction "3_3") (pintype "passive"))
      (node (ref "Q12") (pin "3") (pinfunction "D_3") (pintype "bidirectional"))
    )
    (net (code "22") (name "DROPPER2_GATE") (class "Default")
      (node (ref "Q12") (pin "1") (pinfunction "G_1") (pintype "bidirectional"))
      (node (ref "U$9") (pin "P$32") (pinfunction "GPIO21_P$32") (pintype "bidirectional"))
    )
    (net (code "23") (name "EXTRA1") (class "Default")
      (node (ref "U$1") (pin "28") (pinfunction "SPARE2_28") (pintype "bidirectional"))
    )
    (net (code "26") (name "EXTRA5") (class "Default")
      (node (ref "U$1") (pin "36") (pinfunction "SPARE6_36") (pintype "bidirectional"))
    )
    (net (code "27") (name "EXTRA6") (class "Default")
      (node (ref "U$1") (pin "35") (pinfunction "SPARE5_35") (pintype "bidirectional"))
    )
    (net (code "28") (name "LED1") (class "Default")
      (node (ref "LIGHT1") (pin "A") (pinfunction "A_A") (pintype "passive"))
      (node (ref "U$9") (pin "P$6") (pinfunction "GPIO4_P$6") (pintype "bidirectional"))
    )
    (net (code "29") (name "LED2") (class "Default")
      (node (ref "LIGHT2") (pin "A") (pinfunction "A_A") (pintype "passive"))
      (node (ref "U$9") (pin "P$7") (pinfunction "GPIO5_P$7") (pintype "bidirectional"))
    )
    (net (code "30") (name "Net-(120-1)") (class "Default")
      (node (ref "120") (pin "P$1") (pinfunction "1_P$1") (pintype "passive"))
      (node (ref "C5") (pin "1") (pinfunction "1_1") (pintype "passive"))
      (node (ref "U$6") (pin "P$6") (pinfunction "VOUT_P$6") (pintype "bidirectional"))
    )
    (net (code "31") (name "Net-(ARMED-PadA)") (class "Default")
      (node (ref "ARMED") (pin "A") (pinfunction "A_A") (pintype "passive"))
      (node (ref "R20") (pin "1") (pinfunction "1_1") (pintype "passive"))
    )
    (net (code "32") (name "Net-(C3-Pad1)") (class "Default")
      (node (ref "C3") (pin "1") (pinfunction "1_1") (pintype "passive"))
      (node (ref "R5") (pin "2") (pinfunction "2_2") (pintype "passive"))
      (node (ref "Y2") (pin "2") (pinfunction "2_2") (pintype "passive"))
    )
    (net (code "33") (name "Net-(CHARGING-PadC)") (class "Default")
      (node (ref "CHARGING") (pin "C") (pinfunction "C_C") (pintype "passive"))
      (node (ref "R14") (pin "2") (pinfunction "2_2") (pintype "passive"))
    )
    (net (code "34") (name "Net-(DISCHARGING-PadC)") (class "Default")
      (node (ref "DISCHARGING") (pin "C") (pinfunction "C_C") (pintype "passive"))
      (node (ref "R17") (pin "2") (pinfunction "2_2") (pintype "passive"))
    )
    (net (code "35") (name "Net-(LIGHT1-PadC)") (class "Default")
      (node (ref "LIGHT1") (pin "C") (pinfunction "C_C") (pintype "passive"))
      (node (ref "R18") (pin "2") (pinfunction "2_2") (pintype "passive"))
    )
    (net (code "36") (name "Net-(LIGHT2-PadC)") (class "Default")
      (node (ref "LIGHT2") (pin "C") (pinfunction "C_C") (pintype "passive"))
      (node (ref "R19") (pin "2") (pinfunction "2_2") (pintype "passive"))
    )
    (net (code "37") (name "Net-(Q2-D)") (class "Default")
      (node (ref "Q2") (pin "3") (pinfunction "D_3") (pintype "bidirectional"))
      (node (ref "R44") (pin "1") (pinfunction "1_1") (pintype "passive"))
    )
    (net (code "38") (name "Net-(Q3-D)") (class "Default")
      (node (ref "Q3") (pin "3") (pinfunction "D_3") (pintype "bidirectional"))
      (node (ref "R12") (pin "1") (pinfunction "1_1") (pintype "passive"))
    )
    (net (code "39") (name "Net-(Q6-G)") (class "Default")
      (node (ref "Q6") (pin "1") (pinfunction "G_1") (pintype "passive"))
      (node (ref "R12") (pin "2") (pinfunction "2_2") (pintype "passive"))
      (node (ref "R9") (pin "1") (pinfunction "1_1") (pintype "passive"))
    )
    (net (code "40") (name "Net-(Q18-G)") (class "Default")
      (node (ref "Q18") (pin "1") (pinfunction "G_1") (pintype "passive"))
      (node (ref "R43") (pin "1") (pinfunction "1_1") (pintype "passive"))
      (node (ref "R44") (pin "2") (pinfunction "2_2") (pintype "passive"))
    )
    (net (code "41") (name "Net-(R1-Pad1)") (class "Default")
      (node (ref "R1") (pin "1") (pinfunction "1_1") (pintype "passive"))
      (node (ref "USB_ID/USB_DP/USB_DN") (pin "D+") (pinfunction "D+_D+") (pintype "bidirectional"))
    )
    (net (code "42") (name "Net-(R10-Pad1)") (class "Default")
      (node (ref "R10") (pin "1") (pinfunction "1_1") (pintype "passive"))
      (node (ref "USB_BOOT") (pin "1") (pinfunction "1_1") (pintype "passive"))
    )
    (net (code "43") (name "Net-(R11-Pad1)") (class "Default")
      (node (ref "R11") (pin "1") (pinfunction "1_1") (pintype "passive"))
      (node (ref "USB_ID/USB_DP/USB_DN") (pin "ID") (pinfunction "ID_ID") (pintype "bidirectional"))
    )
    (net (code "44") (name "Net-(R13-Pad1)") (class "Default")
      (node (ref "R13") (pin "1") (pinfunction "1_1") (pintype "passive"))
      (node (ref "USB_ID/USB_DP/USB_DN") (pin "D-") (pinfunction "D-_D-") (pintype "bidirectional"))
    )
    (net (code "45") (name "Net-(U$9-USB_DM)") (class "Default")
      (node (ref "R7") (pin "2") (pinfunction "2_2") (pintype "passive"))
      (node (ref "U$9") (pin "P$46") (pinfunction "USB_DM_P$46") (pintype "bidirectional"))
    )
    (net (code "46") (name "Net-(U$9-USB_DP)") (class "Default")
      (node (ref "R6") (pin "2") (pinfunction "2_2") (pintype "passive"))
      (node (ref "U$9") (pin "P$47") (pinfunction "USB_DP_P$47") (pintype "bidirectional"))
    )
    (net (code "47") (name "Net-(U$9-XIN)") (class "Default")
      (node (ref "C2") (pin "1") (pinfunction "1_1") (pintype "passive"))
      (node (ref "U$9") (pin "P$20") (pinfunction "XIN_P$20") (pintype "bidirectional"))
      (node (ref "Y2") (pin "1") (pinfunction "1_1") (pintype "passive"))
    )
    (net (code "48") (name "Net-(U$9-XOUT)") (class "Default")
      (node (ref "R5") (pin "1") (pinfunction "1_1") (pintype "passive"))
      (node (ref "U$9") (pin "P$21") (pinfunction "XOUT_P$21") (pintype "bidirectional"))
    )
    (net (code "49") (name "Net-(U1-CP1)") (class "Default")
      (node (ref "C18") (pin "2") (pinfunction "2_2") (pintype "passive"))
      (node (ref "U1") (pin "11") (pinfunction "CP1_11") (pintype "passive"))
    )
    (net (code "50") (name "Net-(U1-CP2)") (class "Default")
      (node (ref "C18") (pin "1") (pinfunction "1_1") (pintype "passive"))
      (node (ref "U1") (pin "12") (pinfunction "CP2_12") (pintype "passive"))
    )
    (net (code "51") (name "Net-(U1-SENSE)") (class "Default")
      (node (ref "R4") (pin "2") (pinfunction "2_2") (pintype "passive"))
      (node (ref "U1") (pin "8") (pinfunction "SENSE_8") (pintype "output"))
    )
    (net (code "52") (name "Net-(U1-VBB)") (class "Default")
      (node (ref "C16") (pin "1") (pinfunction "1_1") (pintype "passive"))
      (node (ref "C17") (pin "1") (pinfunction "1_1") (pintype "passive"))
      (node (ref "C19") (pin "1") (pinfunction "1_1") (pintype "passive"))
      (node (ref "U1") (pin "9") (pinfunction "VBB_9") (pintype "power_in"))
    )
    (net (code "53") (name "Net-(U1-VCP)") (class "Default")
      (node (ref "C17") (pin "2") (pinfunction "2_2") (pintype "passive"))
      (node (ref "U1") (pin "14") (pinfunction "VCP_14") (pintype "output"))
    )
    (net (code "54") (name "PWM_CLAW") (class "Default")
      (node (ref "CLAW_CONTROL") (pin "4") (pinfunction "4_4") (pintype "passive"))
      (node (ref "U$9") (pin "P$34") (pinfunction "GPIO22_P$34") (pintype "bidirectional"))
    )
    (net (code "55") (name "PWM_DRIVER1") (class "Default")
      (node (ref "U$9") (pin "P$35") (pinfunction "GPIO23_P$35") (pintype "bidirectional"))
      (node (ref "U1") (pin "3") (pinfunction "IN1_3") (pintype "input"))
    )
    (net (code "56") (name "PWM_DRIVER2") (class "Default")
      (node (ref "U$9") (pin "P$36") (pinfunction "GPIO24_P$36") (pintype "bidirectional"))
      (node (ref "U1") (pin "16") (pinfunction "IN2_16") (pintype "input"))
    )
    (net (code "57") (name "PWM_OUT1") (class "Default")
      (node (ref "CLAW_CONTROL") (pin "5") (pinfunction "5_5") (pintype "passive"))
      (node (ref "U1") (pin "7") (pinfunction "OUT1_7") (pintype "output"))
    )
    (net (code "58") (name "PWM_OUT2") (class "Default")
      (node (ref "CLAW_CONTROL") (pin "6") (pinfunction "6_6") (pintype "passive"))
      (node (ref "U1") (pin "10") (pinfunction "OUT2_10") (pintype "output"))
    )
    (net (code "59") (name "QSPI_SCLK") (class "Default")
      (node (ref "U$9") (pin "P$52") (pinfunction "QSPI_SCLK_P$52") (pintype "bidirectional"))
      (node (ref "U2") (pin "6") (pinfunction "CLK_6") (pintype "input"))
    )
    (net (code "60") (name "QSPI_SD0") (class "Default")
      (node (ref "U$9") (pin "P$53") (pinfunction "QSPI_SD0_P$53") (pintype "bidirectional"))
      (node (ref "U2") (pin "5") (pinfunction "DI(IO0)_5") (pintype "bidirectional"))
    )
    (net (code "61") (name "QSPI_SD1") (class "Default")
      (node (ref "U$9") (pin "P$55") (pinfunction "QSPI_SD1_P$55") (pintype "bidirectional"))
      (node (ref "U2") (pin "2") (pinfunction "DO(IO1)_2") (pintype "bidirectional"))
    )
    (net (code "62") (name "QSPI_SD2") (class "Default")
      (node (ref "U$9") (pin "P$54") (pinfunction "QSPI_SD2_P$54") (pintype "bidirectional"))
      (node (ref "U2") (pin "3") (pinfunction "~{WP(IO2})_3") (pintype "bidirectional"))
    )
    (net (code "63") (name "QSPI_SD3") (class "Default")
      (node (ref "U$9") (pin "P$51") (pinfunction "QSPI_SD3_P$51") (pintype "bidirectional"))
      (node (ref "U2") (pin "7") (pinfunction "~{HOLD(IO3})_7") (pintype "bidirectional"))
    )
    (net (code "64") (name "QSPI_SS") (class "Default")
      (node (ref "C6") (pin "2") (pinfunction "2_2") (pintype "passive"))
      (node (ref "R10") (pin "2") (pinfunction "2_2") (pintype "passive"))
      (node (ref "R8") (pin "1") (pinfunction "1_1") (pintype "passive"))
      (node (ref "U$9") (pin "P$56") (pinfunction "QSPI_SS_P$56") (pintype "bidirectional"))
      (node (ref "U2") (pin "1") (pinfunction "~{CS}_1") (pintype "input"))
    )
    (net (code "65") (name "RESET") (class "Default")
      (node (ref "C36") (pin "2") (pinfunction "2_2") (pintype "passive"))
      (node (ref "JTAG_HEADER") (pin "15") (pinfunction "15_15") (pintype "passive"))
      (node (ref "R27") (pin "1") (pinfunction "1_1") (pintype "passive"))
      (node (ref "RESET_SWITCH") (pin "3") (pinfunction "2_3") (pintype "passive"))
      (node (ref "U$9") (pin "P$26") (pinfunction "RUN_P$26") (pintype "bidirectional"))
    )
    (net (code "66") (name "SCL") (class "Default")
      (node (ref "U$1") (pin "31") (pinfunction "BOARD_SCL_31") (pintype "bidirectional"))
      (node (ref "U$9") (pin "P$3") (pinfunction "GPIO1_P$3") (pintype "bidirectional"))
    )
    (net (code "67") (name "SDA") (class "Default")
      (node (ref "U$1") (pin "32") (pinfunction "BOARD_SDA_32") (pintype "bidirectional"))
      (node (ref "U$9") (pin "P$2") (pinfunction "GPIO0_P$2") (pintype "bidirectional"))
    )
    (net (code "69") (name "SWD_CLK") (class "Default")
      (node (ref "JTAG_HEADER") (pin "9") (pinfunction "9_9") (pintype "passive"))
      (node (ref "U$9") (pin "P$24") (pinfunction "SWCLK_P$24") (pintype "bidirectional"))
    )
    (net (code "70") (name "SWD_IO") (class "Default")
      (node (ref "JTAG_HEADER") (pin "7") (pinfunction "7_7") (pintype "passive"))
      (node (ref "U$9") (pin "P$25") (pinfunction "SWD_P$25") (pintype "bidirectional"))
    )
    (net (code "71") (name "TORPEDO1") (class "Default")
      (node (ref "Q18") (pin "3") (pinfunction "D_3") (pintype "passive"))
      (node (ref "TORPEDO_CONNECTOR") (pin "1") (pinfunction "1_1") (pintype "passive"))
    )
    (net (code "72") (name "TORPEDO1_GATE") (class "Default")
      (node (ref "Q2") (pin "1") (pinfunction "G_1") (pintype "bidirectional"))
      (node (ref "U$9") (pin "P$28") (pinfunction "GPIO17_P$28") (pintype "bidirectional"))
    )
    (net (code "73") (name "TORPEDO2") (class "Default")
      (node (ref "Q6") (pin "3") (pinfunction "D_3") (pintype "passive"))
      (node (ref "TORPEDO_CONNECTOR") (pin "2") (pinfunction "2_2") (pintype "passive"))
    )
    (net (code "74") (name "TORPEDO2_GATE") (class "Default")
      (node (ref "Q3") (pin "1") (pinfunction "G_1") (pintype "bidirectional"))
      (node (ref "U$9") (pin "P$29") (pinfunction "GPIO18_P$29") (pintype "bidirectional"))
    )
    (net (code "75") (name "USB_DN") (class "Default")
      (node (ref "R13") (pin "2") (pinfunction "2_2") (pintype "passive"))
      (node (ref "R7") (pin "1") (pinfunction "1_1") (pintype "passive"))
    )
    (net (code "76") (name "USB_DP") (class "Default")
      (node (ref "R1") (pin "2") (pinfunction "2_2") (pintype "passive"))
      (node (ref "R6") (pin "1") (pinfunction "1_1") (pintype "passive"))
    )
    (net (code "77") (name "USB_ID") (class "Default")
      (node (ref "R11") (pin "2") (pinfunction "2_2") (pintype "passive"))
      (node (ref "R2") (pin "1") (pinfunction "1_1") (pintype "passive"))
    )
    (net (code "78") (name "V+") (class "Default")
      (node (ref "POWER_INPUT") (pin "4") (pinfunction "4_4") (pintype "passive"))
      (node (ref "U$6") (pin "P$2") (pinfunction "VIN_P$2") (pintype "bidirectional"))
    )
    (net (code "79") (name "VBUS") (class "Default")
      (node (ref "C14") (pin "1") (pinfunction "1_1") (pintype "passive"))
      (node (ref "USB_ID/USB_DP/USB_DN") (pin "VBUS") (pinfunction "VBUS_VBUS") (pintype "power_in"))
      (node (ref "VR1") (pin "3") (pinfunction "VIN_3") (pintype "input"))
    )
    (net (code "80") (name "unconnected-(JTAG_HEADER-Pad3)") (class "Default")
      (node (ref "JTAG_HEADER") (pin "3") (pinfunction "3_3") (pintype "passive"))
    )
    (net (code "81") (name "unconnected-(JTAG_HEADER-Pad5)") (class "Default")
      (node (ref "JTAG_HEADER") (pin "5") (pinfunction "5_5") (pintype "passive"))
    )
    (net (code "82") (name "unconnected-(JTAG_HEADER-Pad11)") (class "Default")
      (node (ref "JTAG_HEADER") (pin "11") (pinfunction "11_11") (pintype "passive"))
    )
    (net (code "83") (name "unconnected-(JTAG_HEADER-Pad13)") (class "Default")
      (node (ref "JTAG_HEADER") (pin "13") (pinfunction "13_13") (pintype "passive"))
    )
    (net (code "84") (name "unconnected-(JTAG_HEADER-Pad17)") (class "Default")
      (node (ref "JTAG_HEADER") (pin "17") (pinfunction "17_17") (pintype "passive"))
    )
    (net (code "85") (name "unconnected-(JTAG_HEADER-Pad19)") (class "Default")
      (node (ref "JTAG_HEADER") (pin "19") (pinfunction "19_19") (pintype "passive"))
    )
    (net (code "86") (name "unconnected-(U$1-3.3V_ON{slash}OFF-Pad14)") (class "Default")
      (node (ref "U$1") (pin "14") (pinfunction "3.3V_ON/OFF_14") (pintype "bidirectional"))
    )
    (net (code "87") (name "unconnected-(U$1-5V_ON_OFF-Pad15)") (class "Default")
      (node (ref "U$1") (pin "15") (pinfunction "5V_ON_OFF_15") (pintype "bidirectional"))
    )
    (net (code "88") (name "unconnected-(U$1-12V_ON{slash}OFF-Pad16)") (class "Default")
      (node (ref "U$1") (pin "16") (pinfunction "12V_ON/OFF_16") (pintype "bidirectional"))
    )
    (net (code "89") (name "unconnected-(U$1-ACOUSTIC_ON{slash}OFF-Pad17)") (class "Default")
      (node (ref "U$1") (pin "17") (pinfunction "ACOUSTIC_ON/OFF_17") (pintype "bidirectional"))
    )
    (net (code "90") (name "unconnected-(U$1-JETSON_ON{slash}OFF-Pad18)") (class "Default")
      (node (ref "U$1") (pin "18") (pinfunction "JETSON_ON/OFF_18") (pintype "bidirectional"))
    )
    (net (code "91") (name "unconnected-(U$1-KILL_SWITCH-Pad37)") (class "Default")
      (node (ref "U$1") (pin "37") (pinfunction "KILL_SWITCH_37") (pintype "output"))
    )
    (net (code "92") (name "unconnected-(U$1-MOBO_ON{slash}OFF-Pad19)") (class "Default")
      (node (ref "U$1") (pin "19") (pinfunction "MOBO_ON/OFF_19") (pintype "bidirectional"))
    )
    (net (code "93") (name "unconnected-(U$1-PWM_1-Pad20)") (class "Default")
      (node (ref "U$1") (pin "20") (pinfunction "PWM_1_20") (pintype "bidirectional"))
    )
    (net (code "94") (name "unconnected-(U$1-PWM_2-Pad21)") (class "Default")
      (node (ref "U$1") (pin "21") (pinfunction "PWM_2_21") (pintype "bidirectional"))
    )
    (net (code "95") (name "unconnected-(U$1-PWM_3-Pad22)") (class "Default")
      (node (ref "U$1") (pin "22") (pinfunction "PWM_3_22") (pintype "bidirectional"))
    )
    (net (code "96") (name "unconnected-(U$1-PWM_4-Pad23)") (class "Default")
      (node (ref "U$1") (pin "23") (pinfunction "PWM_4_23") (pintype "bidirectional"))
    )
    (net (code "97") (name "unconnected-(U$1-PWM_5-Pad24)") (class "Default")
      (node (ref "U$1") (pin "24") (pinfunction "PWM_5_24") (pintype "bidirectional"))
    )
    (net (code "98") (name "unconnected-(U$1-PWM_6-Pad25)") (class "Default")
      (node (ref "U$1") (pin "25") (pinfunction "PWM_6_25") (pintype "bidirectional"))
    )
    (net (code "99") (name "unconnected-(U$1-PWM_7-Pad26)") (class "Default")
      (node (ref "U$1") (pin "26") (pinfunction "PWM_7_26") (pintype "bidirectional"))
    )
    (net (code "100") (name "unconnected-(U$1-PWM_8-Pad27)") (class "Default")
      (node (ref "U$1") (pin "27") (pinfunction "PWM_8_27") (pintype "bidirectional"))
    )
    (net (code "101") (name "unconnected-(U$1-SENSOR_SCL-Pad29)") (class "Default")
      (node (ref "U$1") (pin "29") (pinfunction "SENSOR_SCL_29") (pintype "bidirectional"))
    )
    (net (code "102") (name "unconnected-(U$1-SENSOR_SDA-Pad30)") (class "Default")
      (node (ref "U$1") (pin "30") (pinfunction "SENSOR_SDA_30") (pintype "bidirectional"))
    )
    (net (code "103") (name "unconnected-(U$1-SPARE1-Pad7)") (class "Default")
      (node (ref "U$1") (pin "7") (pinfunction "SPARE1_7") (pintype "bidirectional"))
    )
    (net (code "104") (name "unconnected-(U$1-SPARE3-Pad33)") (class "Default")
      (node (ref "U$1") (pin "33") (pinfunction "SPARE3_33") (pintype "bidirectional"))
    )
    (net (code "105") (name "unconnected-(U$1-SPARE4-Pad34)") (class "Default")
      (node (ref "U$1") (pin "34") (pinfunction "SPARE4_34") (pintype "bidirectional"))
    )
    (net (code "106") (name "unconnected-(U$1-SPARE8-Pad50)") (class "Default")
      (node (ref "U$1") (pin "50") (pinfunction "SPARE8_50") (pintype "bidirectional"))
    )
    (net (code "107") (name "unconnected-(U$1-SWITCH_1-Pad38)") (class "Default")
      (node (ref "U$1") (pin "38") (pinfunction "SWITCH_1_38") (pintype "output"))
    )
    (net (code "108") (name "unconnected-(U$1-SWITCH_2-Pad39)") (class "Default")
      (node (ref "U$1") (pin "39") (pinfunction "SWITCH_2_39") (pintype "output"))
    )
    (net (code "109") (name "unconnected-(U$1-SWITCH_3-Pad40)") (class "Default")
      (node (ref "U$1") (pin "40") (pinfunction "SWITCH_3_40") (pintype "output"))
    )
    (net (code "110") (name "unconnected-(U$1-SWITCH_4-Pad41)") (class "Default")
      (node (ref "U$1") (pin "41") (pinfunction "SWITCH_4_41") (pintype "output"))
    )
    (net (code "111") (name "unconnected-(U$1-SWITCH_5-Pad42)") (class "Default")
      (node (ref "U$1") (pin "42") (pinfunction "SWITCH_5_42") (pintype "output"))
    )
    (net (code "112") (name "unconnected-(U$9-GPIO2-PadP$4)") (class "Default")
      (node (ref "U$9") (pin "P$4") (pinfunction "GPIO2_P$4") (pintype "bidirectional"))
    )
    (net (code "113") (name "unconnected-(U$9-GPIO3-PadP$5)") (class "Default")
      (node (ref "U$9") (pin "P$5") (pinfunction "GPIO3_P$5") (pintype "bidirectional"))
    )
    (net (code "114") (name "unconnected-(U$9-GPIO6-PadP$8)") (class "Default")
      (node (ref "U$9") (pin "P$8") (pinfunction "GPIO6_P$8") (pintype "bidirectional"))
    )
    (net (code "115") (name "unconnected-(U$9-GPIO7-PadP$9)") (class "Default")
      (node (ref "U$9") (pin "P$9") (pinfunction "GPIO7_P$9") (pintype "bidirectional"))
    )
    (net (code "116") (name "unconnected-(U$9-GPIO8-PadP$11)") (class "Default")
      (node (ref "U$9") (pin "P$11") (pinfunction "GPIO8_P$11") (pintype "bidirectional"))
    )
    (net (code "117") (name "unconnected-(U$9-GPIO9-PadP$12)") (class "Default")
      (node (ref "U$9") (pin "P$12") (pinfunction "GPIO9_P$12") (pintype "bidirectional"))
    )
    (net (code "118") (name "unconnected-(U$9-GPIO10-PadP$13)") (class "Default")
      (node (ref "U$9") (pin "P$13") (pinfunction "GPIO10_P$13") (pintype "bidirectional"))
    )
    (net (code "119") (name "unconnected-(U$9-GPIO25-PadP$37)") (class "Default")
      (node (ref "U$9") (pin "P$37") (pinfunction "GPIO25_P$37") (pintype "bidirectional"))
    )
    (net (code "120") (name "unconnected-(U$9-GPIO26-PadP$38)") (class "Default")
      (node (ref "U$9") (pin "P$38") (pinfunction "GPIO26_P$38") (pintype "bidirectional"))
    )
    (net (code "121") (name "unconnected-(U$9-GPIO27-PadP$39)") (class "Default")
      (node (ref "U$9") (pin "P$39") (pinfunction "GPIO27_P$39") (pintype "bidirectional"))
    )
    (net (code "122") (name "unconnected-(U$9-GPIO28-PadP$40)") (class "Default")
      (node (ref "U$9") (pin "P$40") (pinfunction "GPIO28_P$40") (pintype "bidirectional"))
    )
    (net (code "123") (name "unconnected-(U$9-GPIO29-PadP$41)") (class "Default")
      (node (ref "U$9") (pin "P$41") (pinfunction "GPIO29_P$41") (pintype "bidirectional"))
    )
    (net (code "124") (name "unconnected-(U1-NFAULT-Pad1)") (class "Default")
      (node (ref "U1") (pin "1") (pinfunction "NFAULT_1") (pintype "output"))
    )
    (net (code "125") (name "unconnected-(U1-VPROPI-Pad15)") (class "Default")
      (node (ref "U1") (pin "15") (pinfunction "VPROPI_15") (pintype "output"))
    )
    (net (code "126") (name "unconnected-(U2-EPAD-Pad9)") (class "Default")
      (node (ref "U2") (pin "9") (pinfunction "EPAD_9") (pintype "passive"))
    )
    (net (code "127") (name "unconnected-(VR1-VOUT_4-Pad4)") (class "Default")
      (node (ref "VR1") (pin "4") (pinfunction "VOUT_4_4") (pintype "output"))
    )
  )
)
